# DCDC-Relay.net
KiCad netlist of a schematic drawn in EAGLE
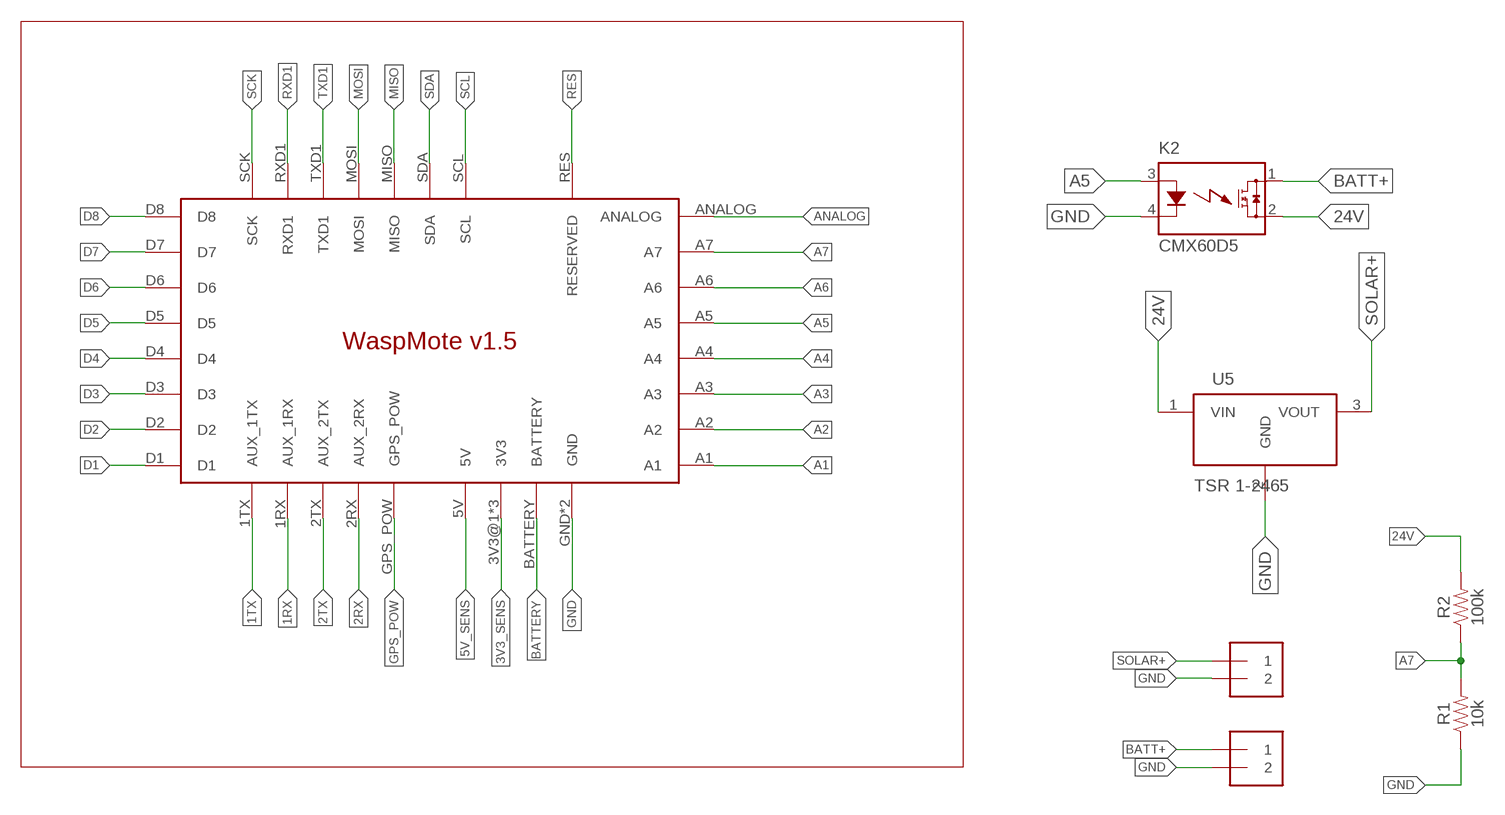
[diagram p0: schematic, sheet 1]

(export (version "E")
  (design (tool "Eeschema 10.0.6"))
  (components
    (comp (ref "J1")
      (value "1X2-3.5MM")
      (footprint "eagle-import:1X2-3.5MM")
      (libsource (lib "eagle-import") (part "1X2-3.5MM"))
    )
    (comp (ref "J2")
      (value "1X2-3.5MM")
      (footprint "eagle-import:1X2-3.5MM")
      (libsource (lib "eagle-import") (part "1X2-3.5MM"))
    )
    (comp (ref "K2")
      (value "CMX60D5")
      (footprint "eagle-import:CMX60D5")
      (libsource (lib "eagle-import") (part "CMX60D5"))
    )
    (comp (ref "R1")
      (value "10k")
      (footprint "eagle-import:AXIAL-0.3")
      (libsource (lib "eagle-import") (part "10KOHM-HORIZ-1/4W-5%"))
    )
    (comp (ref "R2")
      (value "100k")
      (footprint "eagle-import:AXIAL-0.3")
      (libsource (lib "eagle-import") (part "100KOHM-HORIZ-1/4W-1%"))
    )
    (comp (ref "U$1")
      (value "WASPMOTE_V1.5")
      (footprint "eagle-import:WASPMOTE_V1.5")
      (libsource (lib "eagle-import") (part "WASPMOTE_V1.5"))
    )
    (comp (ref "U5")
      (value "TSR 1-2465")
      (footprint "eagle-import:173010535")
      (fields
        (field (name "DIGIKEY_PARTNO") "732-173010535-ND")
        (field (name "MANUFACTURER") "Würth Elektronik")
        (field (name "MPN") "173010535")
        (field (name "CREATED_BY") "PCBLayout.com")
      )
      (libsource (lib "eagle-import") (part "173010535"))
    )
  )
  (nets
    (net (code "1") (name "1RX") (class "Default")
      (node (ref "U$1") (pin "1RX") (pinfunction "AUX_1RX_1RX") (pintype "bidirectional"))
    )
    (net (code "2") (name "1TX") (class "Default")
      (node (ref "U$1") (pin "1TX") (pinfunction "AUX_1TX_1TX") (pintype "bidirectional"))
    )
    (net (code "3") (name "2RX") (class "Default")
      (node (ref "U$1") (pin "2RX") (pinfunction "AUX_2RX_2RX") (pintype "bidirectional"))
    )
    (net (code "4") (name "2TX") (class "Default")
      (node (ref "U$1") (pin "2TX") (pinfunction "AUX_2TX_2TX") (pintype "bidirectional"))
    )
    (net (code "5") (name "3V3_SENS") (class "Default")
      (node (ref "U$1") (pin "3V3@1") (pinfunction "3V3_3V3@1") (pintype "bidirectional"))
      (node (ref "U$1") (pin "3V3@2") (pinfunction "3V3_3V3@2") (pintype "bidirectional"))
      (node (ref "U$1") (pin "3V3@3") (pinfunction "3V3_3V3@3") (pintype "bidirectional"))
    )
    (net (code "6") (name "5V_SENS") (class "Default")
      (node (ref "U$1") (pin "5V") (pinfunction "5V_5V") (pintype "bidirectional"))
    )
    (net (code "7") (name "24V") (class "Default")
      (node (ref "K2") (pin "2") (pinfunction "DS2_2") (pintype "passive"))
      (node (ref "R2") (pin "P$2") (pinfunction "2_P$2") (pintype "passive"))
      (node (ref "U5") (pin "1") (pinfunction "VIN_1") (pintype "power_in"))
    )
    (net (code "8") (name "A1") (class "Default")
      (node (ref "U$1") (pin "A1") (pinfunction "A1_A1") (pintype "bidirectional"))
    )
    (net (code "9") (name "A2") (class "Default")
      (node (ref "U$1") (pin "A2") (pinfunction "A2_A2") (pintype "bidirectional"))
    )
    (net (code "10") (name "A3") (class "Default")
      (node (ref "U$1") (pin "A3") (pinfunction "A3_A3") (pintype "bidirectional"))
    )
    (net (code "11") (name "A4") (class "Default")
      (node (ref "U$1") (pin "A4") (pinfunction "A4_A4") (pintype "bidirectional"))
    )
    (net (code "12") (name "A5") (class "Default")
      (node (ref "K2") (pin "3") (pinfunction "A_3") (pintype "passive"))
      (node (ref "U$1") (pin "A5") (pinfunction "A5_A5") (pintype "bidirectional"))
    )
    (net (code "13") (name "A6") (class "Default")
      (node (ref "U$1") (pin "A6") (pinfunction "A6_A6") (pintype "bidirectional"))
    )
    (net (code "14") (name "A7") (class "Default")
      (node (ref "R1") (pin "P$2") (pinfunction "2_P$2") (pintype "passive"))
      (node (ref "R2") (pin "P$1") (pinfunction "1_P$1") (pintype "passive"))
      (node (ref "U$1") (pin "A7") (pinfunction "A7_A7") (pintype "bidirectional"))
    )
    (net (code "15") (name "ANALOG") (class "Default")
      (node (ref "U$1") (pin "ANALOG") (pinfunction "ANALOG_ANALOG") (pintype "bidirectional"))
    )
    (net (code "16") (name "BATT+") (class "Default")
      (node (ref "J1") (pin "1") (pinfunction "1_1") (pintype "passive"))
      (node (ref "K2") (pin "1") (pinfunction "DS1_1") (pintype "passive"))
    )
    (net (code "17") (name "BATTERY") (class "Default")
      (node (ref "U$1") (pin "BATTERY") (pinfunction "BATTERY_BATTERY") (pintype "bidirectional"))
    )
    (net (code "18") (name "D1") (class "Default")
      (node (ref "U$1") (pin "D1") (pinfunction "D1_D1") (pintype "bidirectional"))
    )
    (net (code "19") (name "D2") (class "Default")
      (node (ref "U$1") (pin "D2") (pinfunction "D2_D2") (pintype "bidirectional"))
    )
    (net (code "20") (name "D3") (class "Default")
      (node (ref "U$1") (pin "D3") (pinfunction "D3_D3") (pintype "bidirectional"))
    )
    (net (code "21") (name "D4") (class "Default")
      (node (ref "U$1") (pin "D4") (pinfunction "D4_D4") (pintype "bidirectional"))
    )
    (net (code "22") (name "D5") (class "Default")
      (node (ref "U$1") (pin "D5") (pinfunction "D5_D5") (pintype "bidirectional"))
    )
    (net (code "23") (name "D6") (class "Default")
      (node (ref "U$1") (pin "D6") (pinfunction "D6_D6") (pintype "bidirectional"))
    )
    (net (code "24") (name "D7") (class "Default")
      (node (ref "U$1") (pin "D7") (pinfunction "D7_D7") (pintype "bidirectional"))
    )
    (net (code "25") (name "D8") (class "Default")
      (node (ref "U$1") (pin "D8") (pinfunction "D8_D8") (pintype "bidirectional"))
    )
    (net (code "26") (name "GND") (class "Default")
      (node (ref "J1") (pin "2") (pinfunction "2_2") (pintype "passive"))
      (node (ref "J2") (pin "2") (pinfunction "2_2") (pintype "passive"))
      (node (ref "K2") (pin "4") (pinfunction "K_4") (pintype "passive"))
      (node (ref "R1") (pin "P$1") (pinfunction "1_P$1") (pintype "passive"))
      (node (ref "U$1") (pin "GND") (pinfunction "GND_GND") (pintype "bidirectional"))
      (node (ref "U$1") (pin "GND_2") (pinfunction "GND_GND_2") (pintype "bidirectional"))
      (node (ref "U5") (pin "2") (pinfunction "GND_2") (pintype "power_in"))
    )
    (net (code "27") (name "GPS_POW") (class "Default")
      (node (ref "U$1") (pin "GPS_POW") (pinfunction "GPS_POW_GPS_POW") (pintype "bidirectional"))
    )
    (net (code "28") (name "MISO") (class "Default")
      (node (ref "U$1") (pin "MISO") (pinfunction "MISO_MISO") (pintype "bidirectional"))
    )
    (net (code "29") (name "MOSI") (class "Default")
      (node (ref "U$1") (pin "MOSI") (pinfunction "MOSI_MOSI") (pintype "bidirectional"))
    )
    (net (code "30") (name "RES") (class "Default")
      (node (ref "U$1") (pin "RES") (pinfunction "RESERVED_RES") (pintype "bidirectional"))
    )
    (net (code "31") (name "RXD1") (class "Default")
      (node (ref "U$1") (pin "RXD1") (pinfunction "RXD1_RXD1") (pintype "bidirectional"))
    )
    (net (code "32") (name "SCK") (class "Default")
      (node (ref "U$1") (pin "SCK") (pinfunction "SCK_SCK") (pintype "bidirectional"))
    )
    (net (code "33") (name "SCL") (class "Default")
      (node (ref "U$1") (pin "SCL") (pinfunction "SCL_SCL") (pintype "bidirectional"))
    )
    (net (code "34") (name "SDA") (class "Default")
      (node (ref "U$1") (pin "SDA") (pinfunction "SDA_SDA") (pintype "bidirectional"))
    )
    (net (code "35") (name "SOLAR+") (class "Default")
      (node (ref "J2") (pin "1") (pinfunction "1_1") (pintype "passive"))
      (node (ref "U5") (pin "3") (pinfunction "VOUT_3") (pintype "power_in"))
    )
    (net (code "36") (name "TXD1") (class "Default")
      (node (ref "U$1") (pin "TXD1") (pinfunction "TXD1_TXD1") (pintype "bidirectional"))
    )
  )
)
